# putt_project.net
KiCad netlist of a schematic drawn in EAGLE
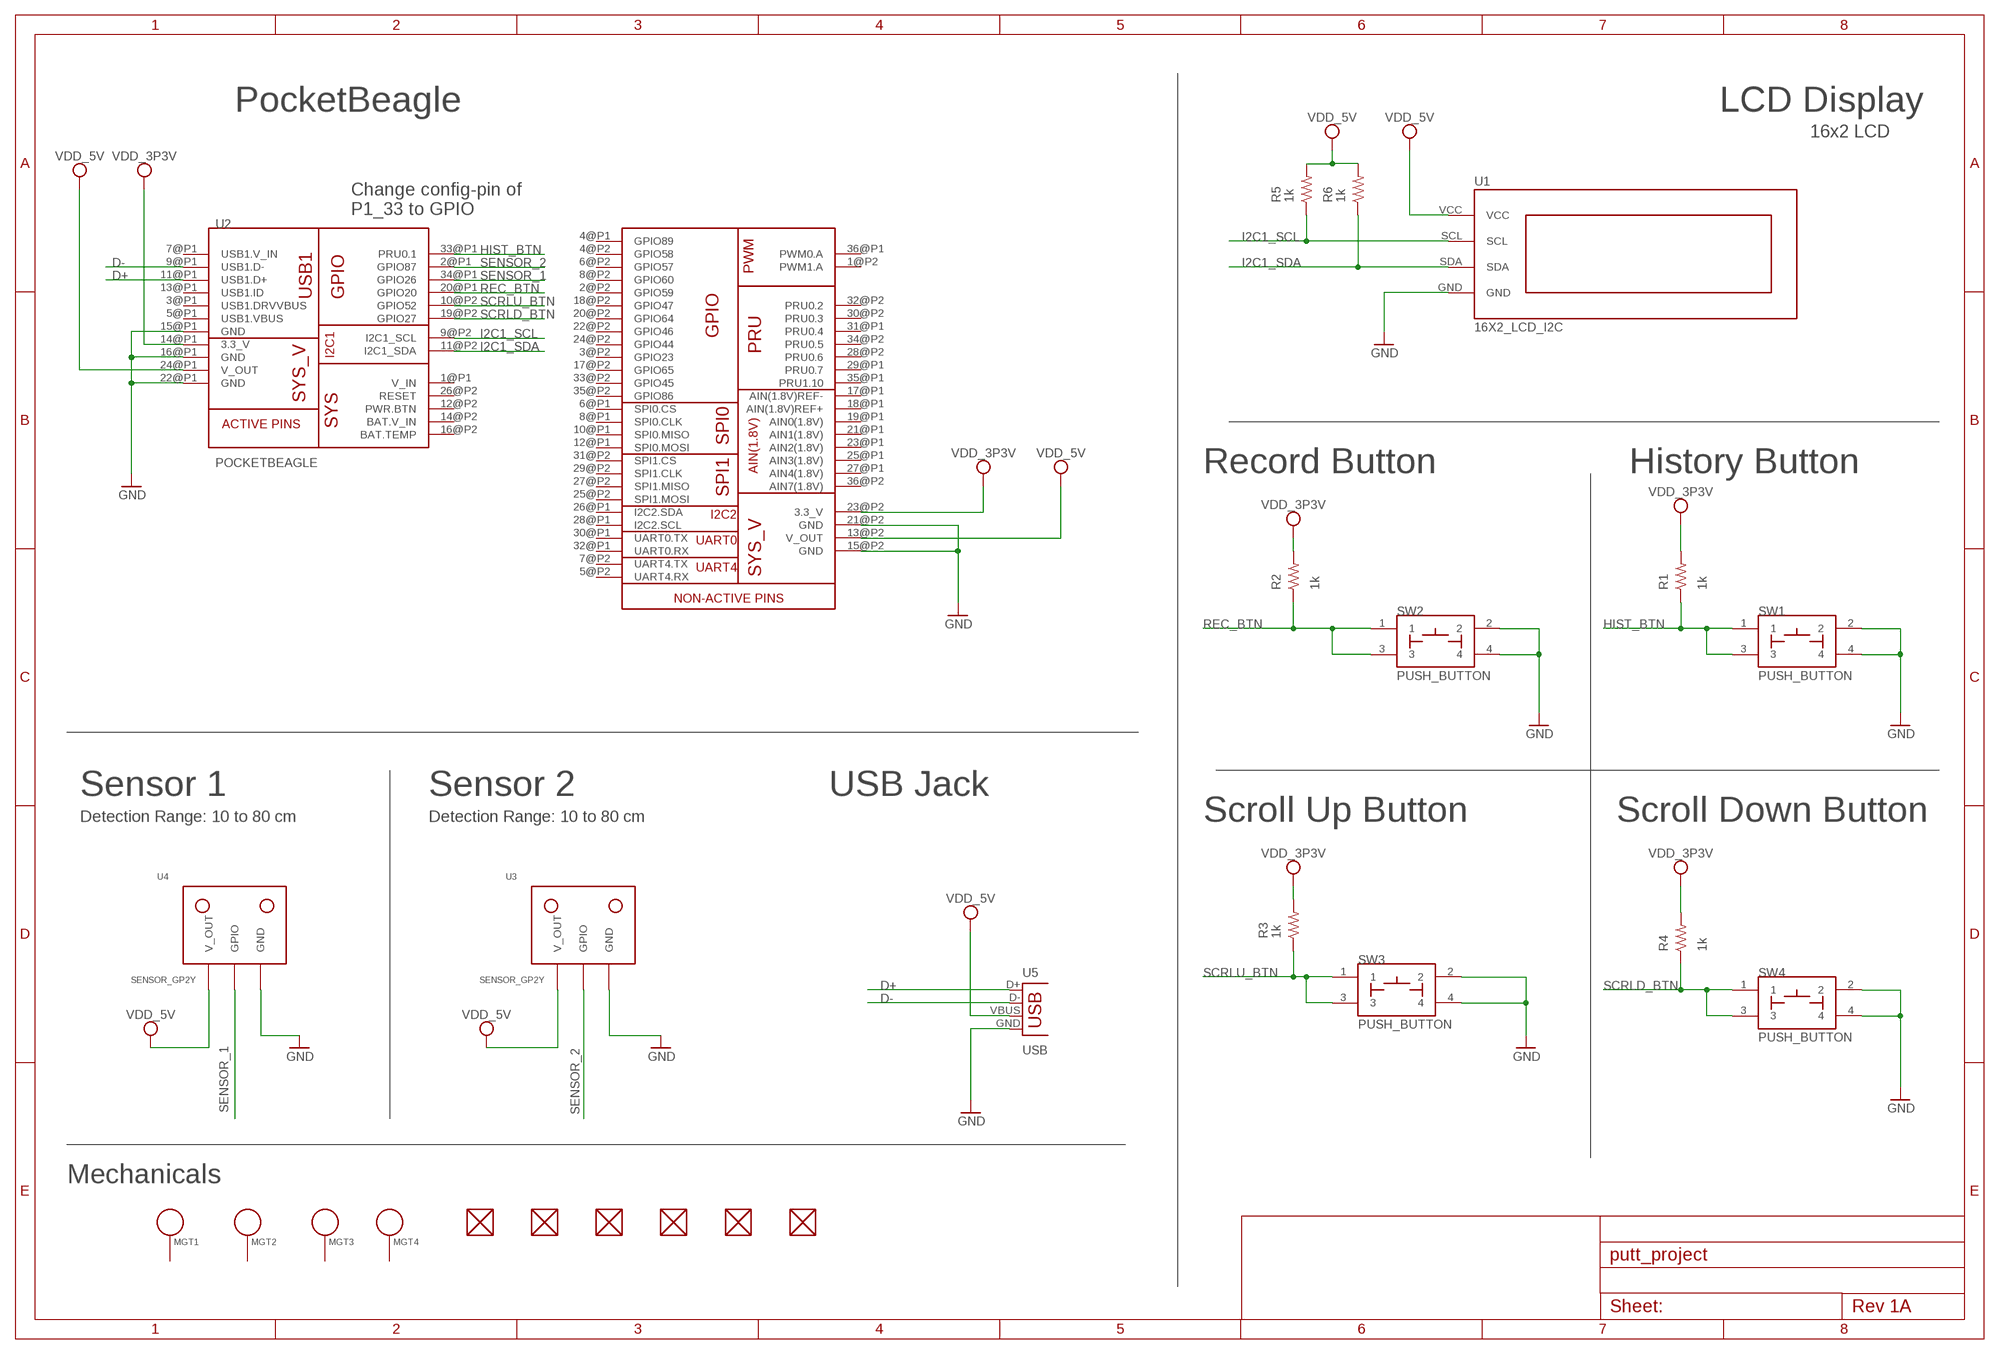
[diagram p0: schematic, sheet 1]

(export (version "E")
  (design (tool "Eeschema 10.0.6"))
  (components
    (comp (ref "FUD1")
      (value "FIDUCIAL")
      (footprint "eagle-import:FIDUCIAL_40MIL")
      (libsource (lib "eagle-import") (part "FIDUCIAL"))
    )
    (comp (ref "FUD2")
      (value "FIDUCIAL")
      (footprint "eagle-import:FIDUCIAL_40MIL")
      (libsource (lib "eagle-import") (part "FIDUCIAL"))
    )
    (comp (ref "FUD3")
      (value "FIDUCIAL")
      (footprint "eagle-import:FIDUCIAL_40MIL")
      (libsource (lib "eagle-import") (part "FIDUCIAL"))
    )
    (comp (ref "FUD4")
      (value "FIDUCIAL")
      (footprint "eagle-import:FIDUCIAL_40MIL")
      (libsource (lib "eagle-import") (part "FIDUCIAL"))
    )
    (comp (ref "FUD5")
      (value "FIDUCIAL")
      (footprint "eagle-import:FIDUCIAL_40MIL")
      (libsource (lib "eagle-import") (part "FIDUCIAL"))
    )
    (comp (ref "FUD6")
      (value "FIDUCIAL")
      (footprint "eagle-import:FIDUCIAL_40MIL")
      (libsource (lib "eagle-import") (part "FIDUCIAL"))
    )
    (comp (ref "MGT1")
      (value "MOUNTING_HOLE")
      (footprint "eagle-import:MOUNTING_HOLE")
      (libsource (lib "eagle-import") (part "MOUNTING_HOLE"))
    )
    (comp (ref "MGT2")
      (value "MOUNTING_HOLE")
      (footprint "eagle-import:MOUNTING_HOLE")
      (libsource (lib "eagle-import") (part "MOUNTING_HOLE"))
    )
    (comp (ref "MGT3")
      (value "MOUNTING_HOLE")
      (footprint "eagle-import:MOUNTING_HOLE")
      (libsource (lib "eagle-import") (part "MOUNTING_HOLE"))
    )
    (comp (ref "MGT4")
      (value "MOUNTING_HOLE")
      (footprint "eagle-import:MOUNTING_HOLE")
      (libsource (lib "eagle-import") (part "MOUNTING_HOLE"))
    )
    (comp (ref "R1")
      (value "1k")
      (footprint "eagle-import:R0603")
      (libsource (lib "eagle-import") (part "R_R0603"))
    )
    (comp (ref "R2")
      (value "1k")
      (footprint "eagle-import:R0603")
      (libsource (lib "eagle-import") (part "R_R0603"))
    )
    (comp (ref "R3")
      (value "1k")
      (footprint "eagle-import:R0603")
      (libsource (lib "eagle-import") (part "R_R0603"))
    )
    (comp (ref "R4")
      (value "1k")
      (footprint "eagle-import:R0603")
      (libsource (lib "eagle-import") (part "R_R0603"))
    )
    (comp (ref "R5")
      (value "1k")
      (footprint "eagle-import:R0603")
      (libsource (lib "eagle-import") (part "R_R0603"))
    )
    (comp (ref "R6")
      (value "1k")
      (footprint "eagle-import:R0603")
      (libsource (lib "eagle-import") (part "R_R0603"))
    )
    (comp (ref "SW1")
      (value "PUSH_BUTTON")
      (footprint "eagle-import:BUTTON_12.5MM")
      (libsource (lib "eagle-import") (part "PUSH_BUTTON"))
    )
    (comp (ref "SW2")
      (value "PUSH_BUTTON")
      (footprint "eagle-import:BUTTON_12.5MM")
      (libsource (lib "eagle-import") (part "PUSH_BUTTON"))
    )
    (comp (ref "SW3")
      (value "PUSH_BUTTON")
      (footprint "eagle-import:BUTTON_12.5MM")
      (libsource (lib "eagle-import") (part "PUSH_BUTTON"))
    )
    (comp (ref "SW4")
      (value "PUSH_BUTTON")
      (footprint "eagle-import:BUTTON_12.5MM")
      (libsource (lib "eagle-import") (part "PUSH_BUTTON"))
    )
    (comp (ref "U1")
      (value "16X2_LCD_I2C")
      (footprint "eagle-import:16X2_LCD_I2C")
      (libsource (lib "eagle-import") (part "16X2_LCD_I2C"))
    )
    (comp (ref "U2")
      (value "POCKETBEAGLE")
      (footprint "eagle-import:POCKETBEAGLE")
      (libsource (lib "eagle-import") (part "POCKETBEAGLE"))
    )
    (comp (ref "U3")
      (value "SENSOR_GP2Y")
      (footprint "eagle-import:SENSOR_IR")
      (libsource (lib "eagle-import") (part "SENSOR_GP2Y"))
    )
    (comp (ref "U4")
      (value "SENSOR_GP2Y")
      (footprint "eagle-import:SENSOR_IR")
      (libsource (lib "eagle-import") (part "SENSOR_GP2Y"))
    )
    (comp (ref "U5")
      (value "USB")
      (footprint "eagle-import:USB-A-H")
      (libsource (lib "eagle-import") (part "USB"))
    )
  )
  (nets
    (net (code "1") (name "/D+") (class "Default")
      (node (ref "U2") (pin "11@P1") (pinfunction "USB1.D+_11@P1") (pintype "bidirectional"))
      (node (ref "U5") (pin "D+") (pinfunction "D+_D+") (pintype "bidirectional"))
    )
    (net (code "2") (name "/D-") (class "Default")
      (node (ref "U2") (pin "9@P1") (pinfunction "USB1.D-_9@P1") (pintype "bidirectional"))
      (node (ref "U5") (pin "D-") (pinfunction "D-_D-") (pintype "bidirectional"))
    )
    (net (code "3") (name "/HIST_BTN") (class "Default")
      (node (ref "R1") (pin "1") (pinfunction "1_1") (pintype "passive"))
      (node (ref "SW1") (pin "1") (pinfunction "1_1") (pintype "bidirectional"))
      (node (ref "SW1") (pin "3") (pinfunction "3_3") (pintype "bidirectional"))
      (node (ref "U2") (pin "33@P1") (pinfunction "PRU0.1_33@P1") (pintype "bidirectional"))
    )
    (net (code "4") (name "/I2C1_SCL") (class "Default")
      (node (ref "R5") (pin "1") (pinfunction "1_1") (pintype "passive"))
      (node (ref "U1") (pin "SCL") (pinfunction "SCL_SCL") (pintype "bidirectional"))
      (node (ref "U2") (pin "9@P2") (pinfunction "I2C1_SCL_9@P2") (pintype "bidirectional"))
    )
    (net (code "5") (name "/I2C1_SDA") (class "Default")
      (node (ref "R6") (pin "1") (pinfunction "1_1") (pintype "passive"))
      (node (ref "U1") (pin "SDA") (pinfunction "SDA_SDA") (pintype "bidirectional"))
      (node (ref "U2") (pin "11@P2") (pinfunction "I2C1_SDA_11@P2") (pintype "bidirectional"))
    )
    (net (code "6") (name "/REC_BTN") (class "Default")
      (node (ref "R2") (pin "1") (pinfunction "1_1") (pintype "passive"))
      (node (ref "SW2") (pin "1") (pinfunction "1_1") (pintype "bidirectional"))
      (node (ref "SW2") (pin "3") (pinfunction "3_3") (pintype "bidirectional"))
      (node (ref "U2") (pin "20@P1") (pinfunction "GPIO20_20@P1") (pintype "bidirectional"))
    )
    (net (code "7") (name "/SCRLD_BTN") (class "Default")
      (node (ref "R4") (pin "1") (pinfunction "1_1") (pintype "passive"))
      (node (ref "SW4") (pin "1") (pinfunction "1_1") (pintype "bidirectional"))
      (node (ref "SW4") (pin "3") (pinfunction "3_3") (pintype "bidirectional"))
      (node (ref "U2") (pin "19@P2") (pinfunction "GPIO27_19@P2") (pintype "bidirectional"))
    )
    (net (code "8") (name "/SCRLU_BTN") (class "Default")
      (node (ref "R3") (pin "1") (pinfunction "1_1") (pintype "passive"))
      (node (ref "SW3") (pin "1") (pinfunction "1_1") (pintype "bidirectional"))
      (node (ref "SW3") (pin "3") (pinfunction "3_3") (pintype "bidirectional"))
      (node (ref "U2") (pin "10@P2") (pinfunction "GPIO52_10@P2") (pintype "bidirectional"))
    )
    (net (code "9") (name "/SENSOR_1") (class "Default")
      (node (ref "U2") (pin "34@P1") (pinfunction "GPIO26_34@P1") (pintype "bidirectional"))
      (node (ref "U4") (pin "GPIO") (pinfunction "GPIO_GPIO") (pintype "bidirectional"))
    )
    (net (code "10") (name "/SENSOR_2") (class "Default")
      (node (ref "U2") (pin "2@P1") (pinfunction "GPIO87_2@P1") (pintype "bidirectional"))
      (node (ref "U3") (pin "GPIO") (pinfunction "GPIO_GPIO") (pintype "bidirectional"))
    )
    (net (code "11") (name "GND") (class "Default")
      (node (ref "SW1") (pin "2") (pinfunction "2_2") (pintype "bidirectional"))
      (node (ref "SW1") (pin "4") (pinfunction "4_4") (pintype "bidirectional"))
      (node (ref "SW2") (pin "2") (pinfunction "2_2") (pintype "bidirectional"))
      (node (ref "SW2") (pin "4") (pinfunction "4_4") (pintype "bidirectional"))
      (node (ref "SW3") (pin "2") (pinfunction "2_2") (pintype "bidirectional"))
      (node (ref "SW3") (pin "4") (pinfunction "4_4") (pintype "bidirectional"))
      (node (ref "SW4") (pin "2") (pinfunction "2_2") (pintype "bidirectional"))
      (node (ref "SW4") (pin "4") (pinfunction "4_4") (pintype "bidirectional"))
      (node (ref "U1") (pin "GND") (pinfunction "GND_GND") (pintype "bidirectional"))
      (node (ref "U2") (pin "15@P1") (pinfunction "GND_15@P1") (pintype "bidirectional"))
      (node (ref "U2") (pin "15@P2") (pinfunction "GND_15@P2") (pintype "bidirectional"))
      (node (ref "U2") (pin "16@P1") (pinfunction "GND_16@P1") (pintype "bidirectional"))
      (node (ref "U2") (pin "21@P2") (pinfunction "GND_21@P2") (pintype "bidirectional"))
      (node (ref "U2") (pin "22@P1") (pinfunction "GND_22@P1") (pintype "bidirectional"))
      (node (ref "U3") (pin "GND") (pinfunction "GND_GND") (pintype "bidirectional"))
      (node (ref "U4") (pin "GND") (pinfunction "GND_GND") (pintype "bidirectional"))
      (node (ref "U5") (pin "GND") (pinfunction "GND_GND") (pintype "bidirectional"))
    )
    (net (code "12") (name "VDD_3P3V") (class "Default")
      (node (ref "R1") (pin "2") (pinfunction "2_2") (pintype "passive"))
      (node (ref "R2") (pin "2") (pinfunction "2_2") (pintype "passive"))
      (node (ref "R3") (pin "2") (pinfunction "2_2") (pintype "passive"))
      (node (ref "R4") (pin "2") (pinfunction "2_2") (pintype "passive"))
      (node (ref "U2") (pin "14@P1") (pinfunction "3.3_V_14@P1") (pintype "bidirectional"))
      (node (ref "U2") (pin "23@P2") (pinfunction "3.3_V_23@P2") (pintype "bidirectional"))
    )
    (net (code "13") (name "VDD_5V") (class "Default")
      (node (ref "R5") (pin "2") (pinfunction "2_2") (pintype "passive"))
      (node (ref "R6") (pin "2") (pinfunction "2_2") (pintype "passive"))
      (node (ref "U1") (pin "VCC") (pinfunction "VCC_VCC") (pintype "power_in"))
      (node (ref "U2") (pin "13@P2") (pinfunction "V_OUT_13@P2") (pintype "bidirectional"))
      (node (ref "U2") (pin "24@P1") (pinfunction "V_OUT_24@P1") (pintype "bidirectional"))
      (node (ref "U3") (pin "PWR") (pinfunction "V_OUT_PWR") (pintype "bidirectional"))
      (node (ref "U4") (pin "PWR") (pinfunction "V_OUT_PWR") (pintype "bidirectional"))
      (node (ref "U5") (pin "VBUS") (pinfunction "VBUS_VBUS") (pintype "bidirectional"))
    )
    (net (code "14") (name "unconnected-(FUD1-PadP$1)") (class "Default")
      (node (ref "FUD1") (pin "P$1") (pinfunction "P$1_P$1") (pintype "no_connect"))
    )
    (net (code "15") (name "unconnected-(FUD2-PadP$1)") (class "Default")
      (node (ref "FUD2") (pin "P$1") (pinfunction "P$1_P$1") (pintype "no_connect"))
    )
    (net (code "16") (name "unconnected-(FUD3-PadP$1)") (class "Default")
      (node (ref "FUD3") (pin "P$1") (pinfunction "P$1_P$1") (pintype "no_connect"))
    )
    (net (code "17") (name "unconnected-(FUD4-PadP$1)") (class "Default")
      (node (ref "FUD4") (pin "P$1") (pinfunction "P$1_P$1") (pintype "no_connect"))
    )
    (net (code "18") (name "unconnected-(FUD5-PadP$1)") (class "Default")
      (node (ref "FUD5") (pin "P$1") (pinfunction "P$1_P$1") (pintype "no_connect"))
    )
    (net (code "19") (name "unconnected-(FUD6-PadP$1)") (class "Default")
      (node (ref "FUD6") (pin "P$1") (pinfunction "P$1_P$1") (pintype "no_connect"))
    )
    (net (code "20") (name "unconnected-(MGT1-PadP$1)") (class "Default")
      (node (ref "MGT1") (pin "P$1") (pinfunction "P$1_P$1") (pintype "bidirectional"))
    )
    (net (code "21") (name "unconnected-(MGT2-PadP$1)") (class "Default")
      (node (ref "MGT2") (pin "P$1") (pinfunction "P$1_P$1") (pintype "bidirectional"))
    )
    (net (code "22") (name "unconnected-(MGT3-PadP$1)") (class "Default")
      (node (ref "MGT3") (pin "P$1") (pinfunction "P$1_P$1") (pintype "bidirectional"))
    )
    (net (code "23") (name "unconnected-(MGT4-PadP$1)") (class "Default")
      (node (ref "MGT4") (pin "P$1") (pinfunction "P$1_P$1") (pintype "bidirectional"))
    )
    (net (code "24") (name "unconnected-(U2-AIN(1.8V)REF+-Pad18@P1)") (class "Default")
      (node (ref "U2") (pin "18@P1") (pinfunction "AIN(1.8V)REF+_18@P1") (pintype "bidirectional"))
    )
    (net (code "25") (name "unconnected-(U2-AIN(1.8V)REF--Pad17@P1)") (class "Default")
      (node (ref "U2") (pin "17@P1") (pinfunction "AIN(1.8V)REF-_17@P1") (pintype "bidirectional"))
    )
    (net (code "26") (name "unconnected-(U2-AIN0(1.8V)-Pad19@P1)") (class "Default")
      (node (ref "U2") (pin "19@P1") (pinfunction "AIN0(1.8V)_19@P1") (pintype "bidirectional"))
    )
    (net (code "27") (name "unconnected-(U2-AIN1(1.8V)-Pad21@P1)") (class "Default")
      (node (ref "U2") (pin "21@P1") (pinfunction "AIN1(1.8V)_21@P1") (pintype "bidirectional"))
    )
    (net (code "28") (name "unconnected-(U2-AIN2(1.8V)-Pad23@P1)") (class "Default")
      (node (ref "U2") (pin "23@P1") (pinfunction "AIN2(1.8V)_23@P1") (pintype "bidirectional"))
    )
    (net (code "29") (name "unconnected-(U2-AIN3(1.8V)-Pad25@P1)") (class "Default")
      (node (ref "U2") (pin "25@P1") (pinfunction "AIN3(1.8V)_25@P1") (pintype "bidirectional"))
    )
    (net (code "30") (name "unconnected-(U2-AIN4(1.8V)-Pad27@P1)") (class "Default")
      (node (ref "U2") (pin "27@P1") (pinfunction "AIN4(1.8V)_27@P1") (pintype "bidirectional"))
    )
    (net (code "31") (name "unconnected-(U2-AIN7(1.8V)-Pad36@P2)") (class "Default")
      (node (ref "U2") (pin "36@P2") (pinfunction "AIN7(1.8V)_36@P2") (pintype "bidirectional"))
    )
    (net (code "32") (name "unconnected-(U2-BAT.TEMP-Pad16@P2)") (class "Default")
      (node (ref "U2") (pin "16@P2") (pinfunction "BAT.TEMP_16@P2") (pintype "bidirectional"))
    )
    (net (code "33") (name "unconnected-(U2-BAT.V_IN-Pad14@P2)") (class "Default")
      (node (ref "U2") (pin "14@P2") (pinfunction "BAT.V_IN_14@P2") (pintype "bidirectional"))
    )
    (net (code "34") (name "unconnected-(U2-GPIO23-Pad3@P2)") (class "Default")
      (node (ref "U2") (pin "3@P2") (pinfunction "GPIO23_3@P2") (pintype "bidirectional"))
    )
    (net (code "35") (name "unconnected-(U2-GPIO44-Pad24@P2)") (class "Default")
      (node (ref "U2") (pin "24@P2") (pinfunction "GPIO44_24@P2") (pintype "bidirectional"))
    )
    (net (code "36") (name "unconnected-(U2-GPIO45-Pad33@P2)") (class "Default")
      (node (ref "U2") (pin "33@P2") (pinfunction "GPIO45_33@P2") (pintype "bidirectional"))
    )
    (net (code "37") (name "unconnected-(U2-GPIO46-Pad22@P2)") (class "Default")
      (node (ref "U2") (pin "22@P2") (pinfunction "GPIO46_22@P2") (pintype "bidirectional"))
    )
    (net (code "38") (name "unconnected-(U2-GPIO47-Pad18@P2)") (class "Default")
      (node (ref "U2") (pin "18@P2") (pinfunction "GPIO47_18@P2") (pintype "bidirectional"))
    )
    (net (code "39") (name "unconnected-(U2-GPIO57-Pad6@P2)") (class "Default")
      (node (ref "U2") (pin "6@P2") (pinfunction "GPIO57_6@P2") (pintype "bidirectional"))
    )
    (net (code "40") (name "unconnected-(U2-GPIO58-Pad4@P2)") (class "Default")
      (node (ref "U2") (pin "4@P2") (pinfunction "GPIO58_4@P2") (pintype "bidirectional"))
    )
    (net (code "41") (name "unconnected-(U2-GPIO59-Pad2@P2)") (class "Default")
      (node (ref "U2") (pin "2@P2") (pinfunction "GPIO59_2@P2") (pintype "bidirectional"))
    )
    (net (code "42") (name "unconnected-(U2-GPIO60-Pad8@P2)") (class "Default")
      (node (ref "U2") (pin "8@P2") (pinfunction "GPIO60_8@P2") (pintype "bidirectional"))
    )
    (net (code "43") (name "unconnected-(U2-GPIO64-Pad20@P2)") (class "Default")
      (node (ref "U2") (pin "20@P2") (pinfunction "GPIO64_20@P2") (pintype "bidirectional"))
    )
    (net (code "44") (name "unconnected-(U2-GPIO65-Pad17@P2)") (class "Default")
      (node (ref "U2") (pin "17@P2") (pinfunction "GPIO65_17@P2") (pintype "bidirectional"))
    )
    (net (code "45") (name "unconnected-(U2-GPIO86-Pad35@P2)") (class "Default")
      (node (ref "U2") (pin "35@P2") (pinfunction "GPIO86_35@P2") (pintype "bidirectional"))
    )
    (net (code "46") (name "unconnected-(U2-GPIO89-Pad4@P1)") (class "Default")
      (node (ref "U2") (pin "4@P1") (pinfunction "GPIO89_4@P1") (pintype "bidirectional"))
    )
    (net (code "47") (name "unconnected-(U2-I2C2.SCL-Pad28@P1)") (class "Default")
      (node (ref "U2") (pin "28@P1") (pinfunction "I2C2.SCL_28@P1") (pintype "bidirectional"))
    )
    (net (code "48") (name "unconnected-(U2-I2C2.SDA-Pad26@P1)") (class "Default")
      (node (ref "U2") (pin "26@P1") (pinfunction "I2C2.SDA_26@P1") (pintype "bidirectional"))
    )
    (net (code "49") (name "unconnected-(U2-PRU0.2-Pad32@P2)") (class "Default")
      (node (ref "U2") (pin "32@P2") (pinfunction "PRU0.2_32@P2") (pintype "bidirectional"))
    )
    (net (code "50") (name "unconnected-(U2-PRU0.3-Pad30@P2)") (class "Default")
      (node (ref "U2") (pin "30@P2") (pinfunction "PRU0.3_30@P2") (pintype "bidirectional"))
    )
    (net (code "51") (name "unconnected-(U2-PRU0.4-Pad31@P1)") (class "Default")
      (node (ref "U2") (pin "31@P1") (pinfunction "PRU0.4_31@P1") (pintype "bidirectional"))
    )
    (net (code "52") (name "unconnected-(U2-PRU0.5-Pad34@P2)") (class "Default")
      (node (ref "U2") (pin "34@P2") (pinfunction "PRU0.5_34@P2") (pintype "bidirectional"))
    )
    (net (code "53") (name "unconnected-(U2-PRU0.6-Pad28@P2)") (class "Default")
      (node (ref "U2") (pin "28@P2") (pinfunction "PRU0.6_28@P2") (pintype "bidirectional"))
    )
    (net (code "54") (name "unconnected-(U2-PRU0.7-Pad29@P1)") (class "Default")
      (node (ref "U2") (pin "29@P1") (pinfunction "PRU0.7_29@P1") (pintype "bidirectional"))
    )
    (net (code "55") (name "unconnected-(U2-PRU1.10-Pad35@P1)") (class "Default")
      (node (ref "U2") (pin "35@P1") (pinfunction "PRU1.10_35@P1") (pintype "bidirectional"))
    )
    (net (code "56") (name "unconnected-(U2-PWM0.A-Pad36@P1)") (class "Default")
      (node (ref "U2") (pin "36@P1") (pinfunction "PWM0.A_36@P1") (pintype "bidirectional"))
    )
    (net (code "57") (name "unconnected-(U2-PWM1.A-Pad1@P2)") (class "Default")
      (node (ref "U2") (pin "1@P2") (pinfunction "PWM1.A_1@P2") (pintype "bidirectional"))
    )
    (net (code "58") (name "unconnected-(U2-PWR.BTN-Pad12@P2)") (class "Default")
      (node (ref "U2") (pin "12@P2") (pinfunction "PWR.BTN_12@P2") (pintype "bidirectional"))
    )
    (net (code "59") (name "unconnected-(U2-RESET-Pad26@P2)") (class "Default")
      (node (ref "U2") (pin "26@P2") (pinfunction "RESET_26@P2") (pintype "bidirectional"))
    )
    (net (code "60") (name "unconnected-(U2-SPI0.CLK-Pad8@P1)") (class "Default")
      (node (ref "U2") (pin "8@P1") (pinfunction "SPI0.CLK_8@P1") (pintype "bidirectional"))
    )
    (net (code "61") (name "unconnected-(U2-SPI0.CS-Pad6@P1)") (class "Default")
      (node (ref "U2") (pin "6@P1") (pinfunction "SPI0.CS_6@P1") (pintype "bidirectional"))
    )
    (net (code "62") (name "unconnected-(U2-SPI0.MISO-Pad10@P1)") (class "Default")
      (node (ref "U2") (pin "10@P1") (pinfunction "SPI0.MISO_10@P1") (pintype "bidirectional"))
    )
    (net (code "63") (name "unconnected-(U2-SPI0.MOSI-Pad12@P1)") (class "Default")
      (node (ref "U2") (pin "12@P1") (pinfunction "SPI0.MOSI_12@P1") (pintype "bidirectional"))
    )
    (net (code "64") (name "unconnected-(U2-SPI1.CLK-Pad29@P2)") (class "Default")
      (node (ref "U2") (pin "29@P2") (pinfunction "SPI1.CLK_29@P2") (pintype "bidirectional"))
    )
    (net (code "65") (name "unconnected-(U2-SPI1.CS-Pad31@P2)") (class "Default")
      (node (ref "U2") (pin "31@P2") (pinfunction "SPI1.CS_31@P2") (pintype "bidirectional"))
    )
    (net (code "66") (name "unconnected-(U2-SPI1.MISO-Pad27@P2)") (class "Default")
      (node (ref "U2") (pin "27@P2") (pinfunction "SPI1.MISO_27@P2") (pintype "bidirectional"))
    )
    (net (code "67") (name "unconnected-(U2-SPI1.MOSI-Pad25@P2)") (class "Default")
      (node (ref "U2") (pin "25@P2") (pinfunction "SPI1.MOSI_25@P2") (pintype "bidirectional"))
    )
    (net (code "68") (name "unconnected-(U2-UART0.RX-Pad32@P1)") (class "Default")
      (node (ref "U2") (pin "32@P1") (pinfunction "UART0.RX_32@P1") (pintype "bidirectional"))
    )
    (net (code "69") (name "unconnected-(U2-UART0.TX-Pad30@P1)") (class "Default")
      (node (ref "U2") (pin "30@P1") (pinfunction "UART0.TX_30@P1") (pintype "bidirectional"))
    )
    (net (code "70") (name "unconnected-(U2-UART4.RX-Pad5@P2)") (class "Default")
      (node (ref "U2") (pin "5@P2") (pinfunction "UART4.RX_5@P2") (pintype "bidirectional"))
    )
    (net (code "71") (name "unconnected-(U2-UART4.TX-Pad7@P2)") (class "Default")
      (node (ref "U2") (pin "7@P2") (pinfunction "UART4.TX_7@P2") (pintype "bidirectional"))
    )
    (net (code "72") (name "unconnected-(U2-USB1.DRVVBUS-Pad3@P1)") (class "Default")
      (node (ref "U2") (pin "3@P1") (pinfunction "USB1.DRVVBUS_3@P1") (pintype "bidirectional"))
    )
    (net (code "73") (name "unconnected-(U2-USB1.ID-Pad13@P1)") (class "Default")
      (node (ref "U2") (pin "13@P1") (pinfunction "USB1.ID_13@P1") (pintype "bidirectional"))
    )
    (net (code "74") (name "unconnected-(U2-USB1.VBUS-Pad5@P1)") (class "Default")
      (node (ref "U2") (pin "5@P1") (pinfunction "USB1.VBUS_5@P1") (pintype "bidirectional"))
    )
    (net (code "75") (name "unconnected-(U2-USB1.V_IN-Pad7@P1)") (class "Default")
      (node (ref "U2") (pin "7@P1") (pinfunction "USB1.V_IN_7@P1") (pintype "bidirectional"))
    )
    (net (code "76") (name "unconnected-(U2-V_IN-Pad1@P1)") (class "Default")
      (node (ref "U2") (pin "1@P1") (pinfunction "V_IN_1@P1") (pintype "bidirectional"))
    )
  )
)
